# Input_Selection.net
KiCad netlist of a schematic drawn in Altium Designer
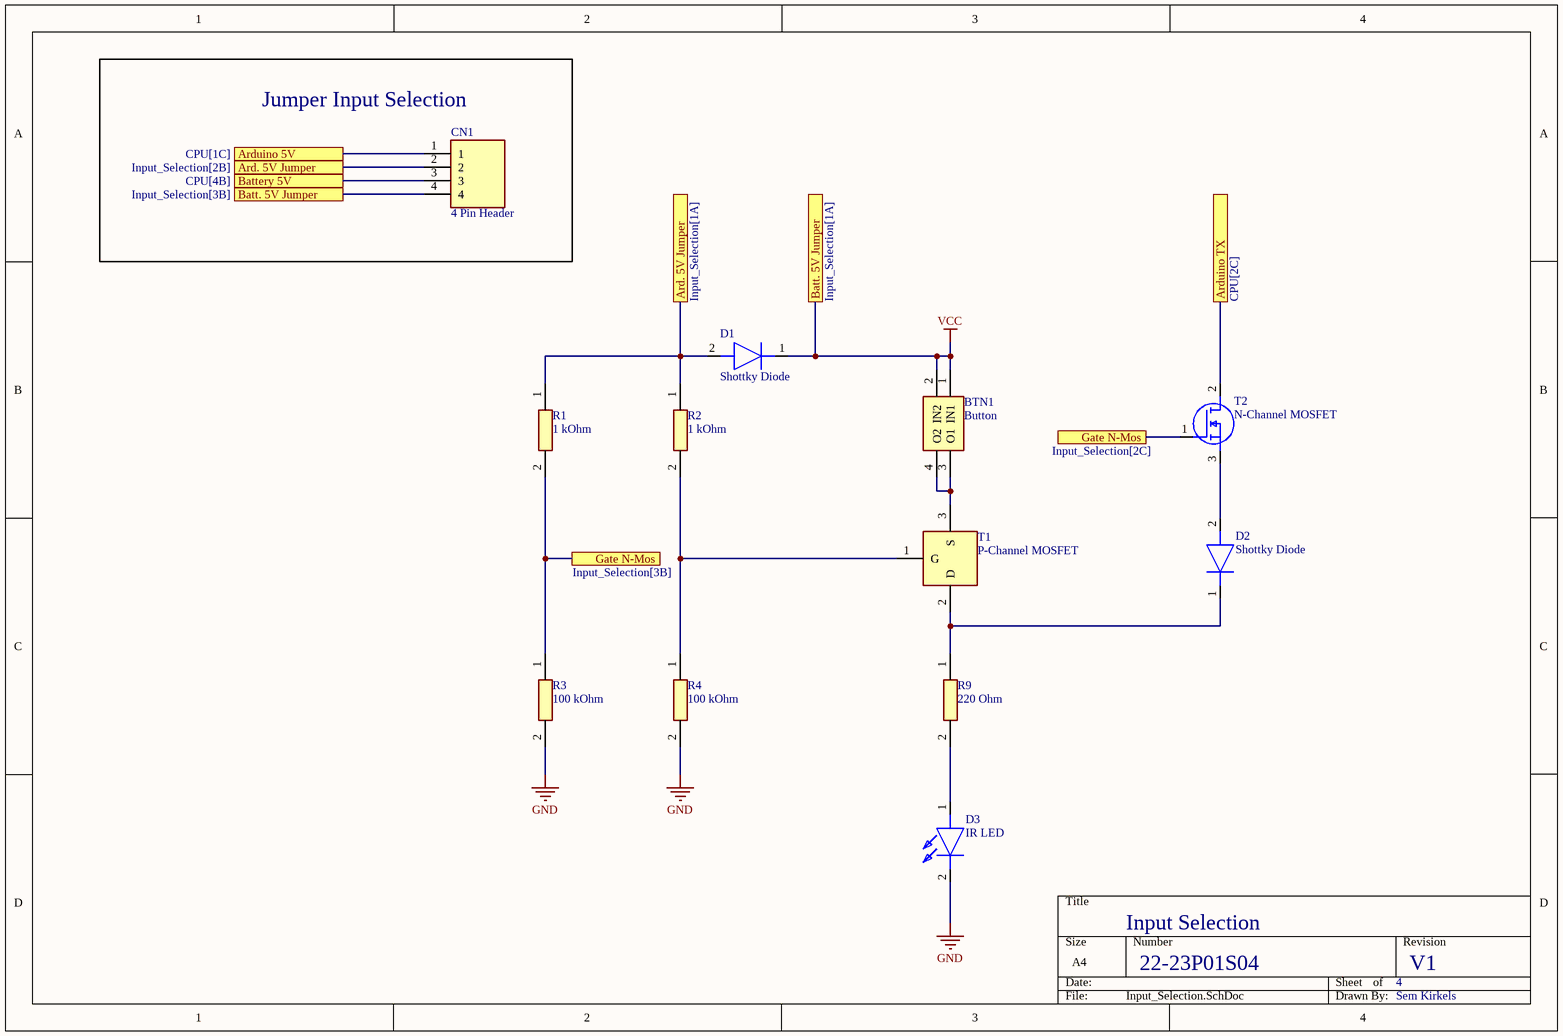
[diagram p0: Input_Selection.SchDoc]

(export (version "E")
  (design (tool "Eeschema 10.0.6"))
  (components
    (comp (ref "BTN1")
      (value "Button")
      (footprint "PushButton")
      (description "TS02-66-50-BK-100-SCR-D")
      (fields (field (name "MOUSER PART NUMBER") "179-TS026650BK100SCR"))
      (libsource (lib "IR_Communication_Schematic_Lib") (part "Button"))
    )
    (comp (ref "CN1")
      (value "4 Pin Header")
      (footprint "4 PIN HEADER")
      (description "G800LW304032EU")
      (fields (field (name "MOUSER PART NUMBER") "523-G800LW304032EU"))
      (libsource (lib "IR_Communication_Schematic_Lib") (part "4 Pin Header"))
    )
    (comp (ref "D1")
      (value "Shottky Diode")
      (footprint "Zener Diode")
      (description "VS-10BQ015-M3_5BT")
      (fields
        (field (name "MANUFACTURER_PART_NUMBER") "VS-10BQ015-M3/5BT")
        (field (name "MOUSER PART NUMBER") "78-VS-10BQ015-M35BT")
      )
      (libsource (lib "IR_Communication_Schematic_Lib") (part "Zener Diode"))
    )
    (comp (ref "D2")
      (value "Shottky Diode")
      (footprint "Zener Diode")
      (description "VS-10BQ015-M3_5BT")
      (fields
        (field (name "MANUFACTURER_PART_NUMBER") "VS-10BQ015-M3/5BT")
        (field (name "MOUSER PART NUMBER") "78-VS-10BQ015-M35BT")
      )
      (libsource (lib "IR_Communication_Schematic_Lib") (part "Zener Diode"))
    )
    (comp (ref "D3")
      (value "IR LED")
      (footprint "SamacSys:ELIR204H16L10")
      (description "LED EL-IR204_H16_L10")
      (fields
        (field (name "MANUFACTURER_PART_NUMBER") "EL-IR204/H16/L10")
        (field (name "MOUSER PART NUMBER") "638-IR204/H16/L10")
      )
      (libsource (lib "IR_Communication_Schematic_Lib") (part "IR LED"))
    )
    (comp (ref "R1")
      (value "1 kOhm")
      (footprint "0805")
      (description "Resistor")
      (fields
        (field (name "MANUFACTURER_PART_NUMBER") "RP0805BRD071KL")
        (field (name "MOUSER PART NUMBER") "603-RP0805BRD071KL")
      )
      (libsource (lib "IR_Communication_Schematic_Lib") (part "Resistor"))
    )
    (comp (ref "R2")
      (value "1 kOhm")
      (footprint "0805")
      (description "Resistor")
      (fields
        (field (name "MANUFACTURER_PART_NUMBER") "RP0805BRD071KL")
        (field (name "MOUSER PART NUMBER") "603-RP0805BRD071KL")
      )
      (libsource (lib "IR_Communication_Schematic_Lib") (part "Resistor"))
    )
    (comp (ref "R3")
      (value "100 kOhm")
      (footprint "0805")
      (description "Resistor")
      (fields
        (field (name "MANUFACTURER_PART_NUMBER") "RP0805BRD071KL")
        (field (name "MOUSER PART NUMBER") "603-RP0805BRD071KL")
      )
      (libsource (lib "IR_Communication_Schematic_Lib") (part "Resistor"))
    )
    (comp (ref "R4")
      (value "100 kOhm")
      (footprint "0805")
      (description "Resistor")
      (fields
        (field (name "MANUFACTURER_PART_NUMBER") "RP0805BRD071KL")
        (field (name "MOUSER PART NUMBER") "603-RP0805BRD071KL")
      )
      (libsource (lib "IR_Communication_Schematic_Lib") (part "Resistor"))
    )
    (comp (ref "R9")
      (value "220 Ohm")
      (footprint "0805")
      (description "Resistor")
      (fields
        (field (name "MANUFACTURER_PART_NUMBER") "RP0805BRD071KL")
        (field (name "MOUSER PART NUMBER") "603-RP0805BRD071KL")
      )
      (libsource (lib "IR_Communication_Schematic_Lib") (part "Resistor"))
    )
    (comp (ref "T1")
      (value "P-Channel MOSFET")
      (footprint "SamacSys:TO254P469X1042X1967-3P")
      (description "MOSFET (P-Channel)IRF9530NPBF")
      (fields
        (field (name "MANUFACTURER_PART_NUMBER") "IRF9530NPBF")
        (field (name "MOUSER PART NUMBER") "942-IRF9530NPBF")
      )
      (libsource (lib "IR_Communication_Schematic_Lib") (part "P-Channel MOSFET"))
    )
    (comp (ref "T2")
      (value "N-Channel MOSFET")
      (footprint "N-MOS")
      (description "MOSFET (N-Channel)IRF540NPBF")
      (fields
        (field (name "MANUFACTURER_PART_NUMBER") "IRF540NPBF")
        (field (name "MOUSER PART NUMBER") "942-IRF540NPBF")
      )
      (libsource (lib "IR_Communication_Schematic_Lib") (part "N-Channel MOSFET"))
    )
  )
  (nets
    (net (code "1") (name "/Ard. 5V Jumper") (class "Default")
      (node (ref "CN1") (pin "2") (pinfunction "2_2") (pintype "passive"))
      (node (ref "D1") (pin "2") (pinfunction "A_2") (pintype "passive"))
      (node (ref "R1") (pin "1") (pinfunction "1_1") (pintype "passive"))
      (node (ref "R2") (pin "1") (pinfunction "1_1") (pintype "passive"))
    )
    (net (code "2") (name "/Arduino 5V") (class "Default")
      (node (ref "CN1") (pin "1") (pinfunction "1_1") (pintype "passive"))
    )
    (net (code "3") (name "/Arduino TX") (class "Default")
      (node (ref "T2") (pin "2") (pinfunction "D_2") (pintype "passive"))
    )
    (net (code "4") (name "/Battery 5V") (class "Default")
      (node (ref "CN1") (pin "3") (pinfunction "3_3") (pintype "passive"))
    )
    (net (code "5") (name "/Gate N-Mos") (class "Default")
      (node (ref "R1") (pin "2") (pinfunction "2_2") (pintype "passive"))
      (node (ref "R3") (pin "1") (pinfunction "1_1") (pintype "passive"))
      (node (ref "T2") (pin "1") (pinfunction "G_1") (pintype "passive"))
    )
    (net (code "6") (name "GND") (class "Default")
      (node (ref "D3") (pin "2") (pinfunction "K_2") (pintype "passive"))
      (node (ref "R3") (pin "2") (pinfunction "2_2") (pintype "passive"))
      (node (ref "R4") (pin "2") (pinfunction "2_2") (pintype "passive"))
    )
    (net (code "7") (name "Net-(BTN1-O1)") (class "Default")
      (node (ref "BTN1") (pin "3") (pinfunction "O1_3") (pintype "passive"))
      (node (ref "BTN1") (pin "4") (pinfunction "O2_4") (pintype "passive"))
      (node (ref "T1") (pin "3") (pinfunction "S_3") (pintype "passive"))
    )
    (net (code "8") (name "Net-(D2-A)") (class "Default")
      (node (ref "D2") (pin "2") (pinfunction "A_2") (pintype "passive"))
      (node (ref "T2") (pin "3") (pinfunction "S_3") (pintype "passive"))
    )
    (net (code "9") (name "Net-(D2-K)") (class "Default")
      (node (ref "D2") (pin "1") (pinfunction "K_1") (pintype "passive"))
      (node (ref "R9") (pin "1") (pinfunction "1_1") (pintype "passive"))
      (node (ref "T1") (pin "2") (pinfunction "D_2") (pintype "passive"))
    )
    (net (code "10") (name "Net-(D3-A)") (class "Default")
      (node (ref "D3") (pin "1") (pinfunction "A_1") (pintype "passive"))
      (node (ref "R9") (pin "2") (pinfunction "2_2") (pintype "passive"))
    )
    (net (code "11") (name "Net-(T1-G)") (class "Default")
      (node (ref "R2") (pin "2") (pinfunction "2_2") (pintype "passive"))
      (node (ref "R4") (pin "1") (pinfunction "1_1") (pintype "passive"))
      (node (ref "T1") (pin "1") (pinfunction "G_1") (pintype "passive"))
    )
    (net (code "12") (name "VCC") (class "Default")
      (node (ref "BTN1") (pin "1") (pinfunction "IN1_1") (pintype "passive"))
      (node (ref "BTN1") (pin "2") (pinfunction "IN2_2") (pintype "passive"))
      (node (ref "CN1") (pin "4") (pinfunction "4_4") (pintype "passive"))
      (node (ref "D1") (pin "1") (pinfunction "K_1") (pintype "passive"))
    )
  )
)
